# ard-nano-thermometer-4digit-display.net
KiCad netlist of a schematic drawn in EAGLE
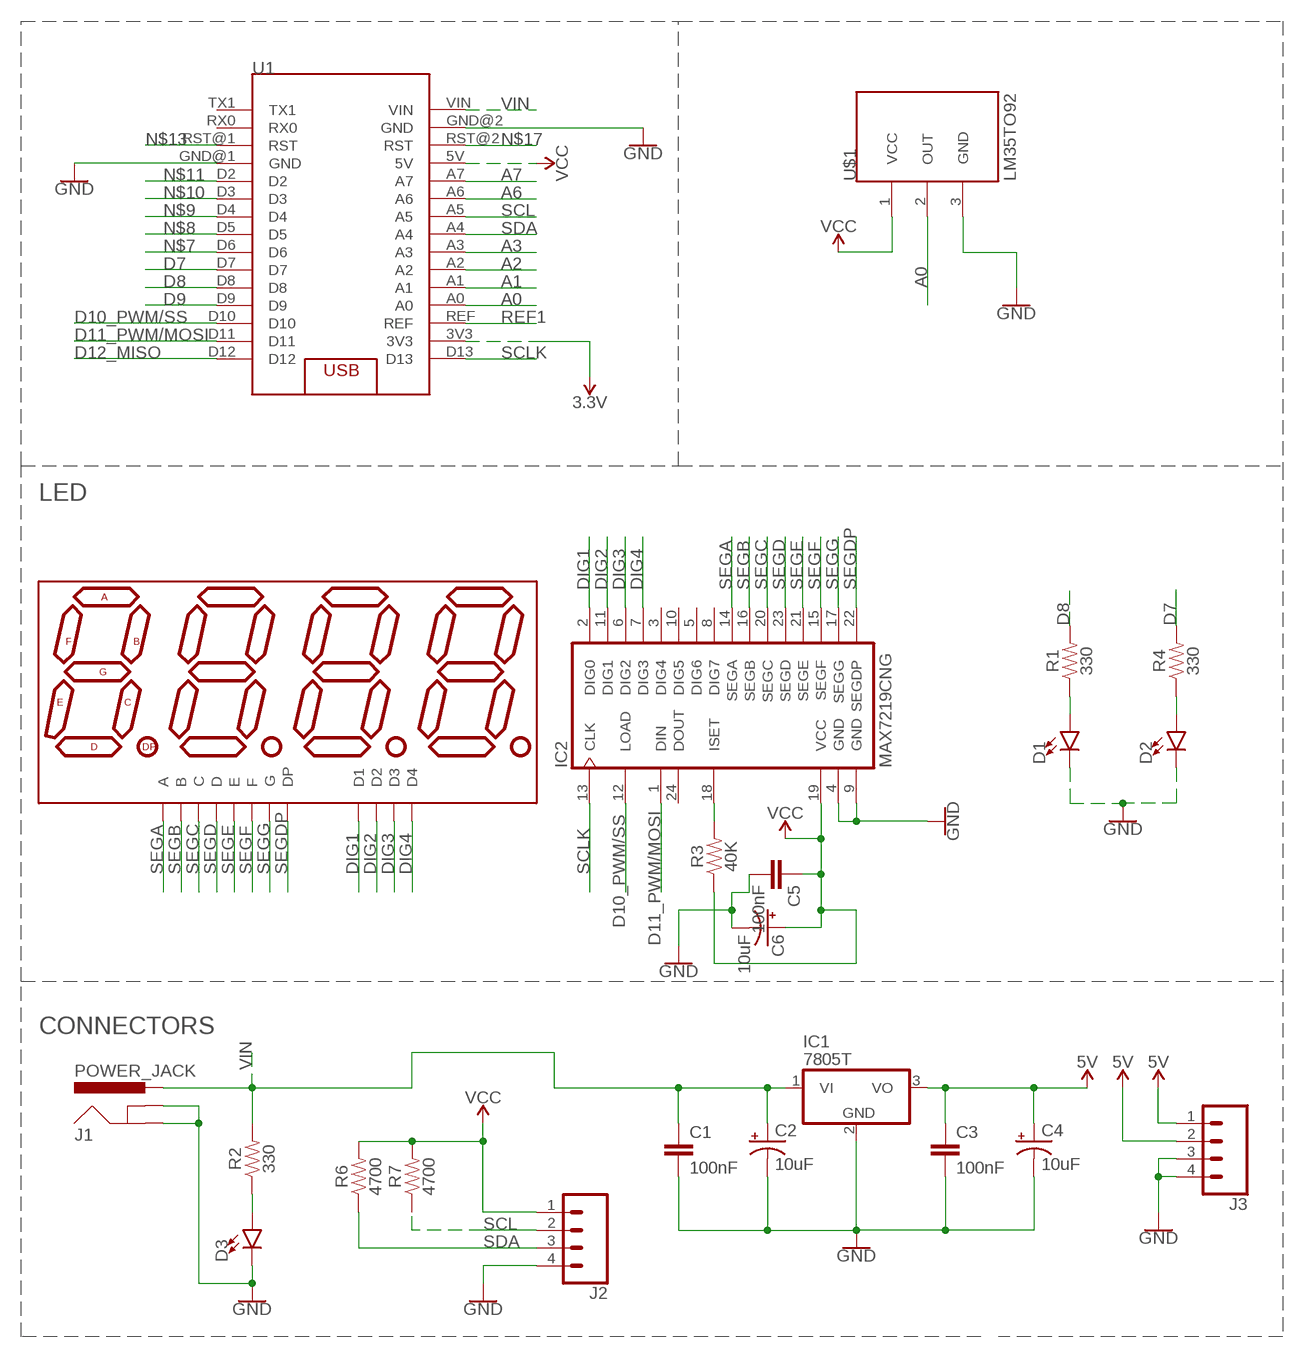
[diagram p0: schematic, sheet 1]

(export (version "E")
  (design (tool "Eeschema 10.0.6"))
  (components
    (comp (ref "C1")
      (value "100nF")
      (footprint "eagle-import:CAP-PTH-10MM")
      (libsource (lib "eagle-import") (part "10NF-PTH-10MM-10000V-1-%"))
    )
    (comp (ref "C2")
      (value "10uF")
      (footprint "eagle-import:CPOL-RADIAL-2.5MM-5MM")
      (libsource (lib "eagle-import") (part "10UF-POLAR-RADIAL-2.5MM-25V-20%"))
    )
    (comp (ref "C3")
      (value "100nF")
      (footprint "eagle-import:CAP-PTH-10MM")
      (libsource (lib "eagle-import") (part "10NF-PTH-10MM-10000V-1-%"))
    )
    (comp (ref "C4")
      (value "10uF")
      (footprint "eagle-import:CPOL-RADIAL-2.5MM-5MM")
      (libsource (lib "eagle-import") (part "10UF-POLAR-RADIAL-2.5MM-25V-20%"))
    )
    (comp (ref "C5")
      (value "100nF")
      (footprint "eagle-import:CAP-PTH-10MM")
      (libsource (lib "eagle-import") (part "10NF-PTH-10MM-10000V-1-%"))
    )
    (comp (ref "C6")
      (value "10uF")
      (footprint "eagle-import:CPOL-RADIAL-2.5MM-5MM")
      (libsource (lib "eagle-import") (part "10UF-POLAR-RADIAL-2.5MM-25V-20%"))
    )
    (comp (ref "D1")
      (value "LED3MM")
      (footprint "eagle-import:LED_3MM")
      (libsource (lib "eagle-import") (part "LED3MM"))
    )
    (comp (ref "D2")
      (value "LED3MM")
      (footprint "eagle-import:LED_3MM")
      (libsource (lib "eagle-import") (part "LED3MM"))
    )
    (comp (ref "D3")
      (value "LED3MM")
      (footprint "eagle-import:LED_3MM")
      (libsource (lib "eagle-import") (part "LED3MM"))
    )
    (comp (ref "DISP1")
      (value "ATA8041AB")
      (footprint "eagle-import:7-SEGMENT-4DIGIT-20MM")
      (libsource (lib "eagle-import") (part "7-SEGMENT-4DIGIT-20MM-BLUE"))
    )
    (comp (ref "IC1")
      (value "7805T")
      (footprint "eagle-import:TO220H")
      (libsource (lib "eagle-import") (part "78T05"))
    )
    (comp (ref "IC2")
      (value "MAX7219CNG")
      (footprint "eagle-import:DIL24-3")
      (fields (field (name "MF") "MAXIM"))
      (libsource (lib "eagle-import") (part "MAX7219CNG"))
    )
    (comp (ref "J1")
      (value "POWER_JACK")
      (footprint "eagle-import:POWER_JACK_PTH")
      (libsource (lib "eagle-import") (part "POWER_JACK"))
    )
    (comp (ref "J2")
      (value "CONN_04PTH")
      (footprint "eagle-import:1X04")
      (libsource (lib "eagle-import") (part "CONN_04PTH"))
    )
    (comp (ref "J3")
      (value "CONN_04PTH")
      (footprint "eagle-import:1X04")
      (libsource (lib "eagle-import") (part "CONN_04PTH"))
    )
    (comp (ref "R1")
      (value "330")
      (footprint "eagle-import:AXIAL-0.3")
      (libsource (lib "eagle-import") (part "1KOHM-HORIZ-1/4W-5%"))
    )
    (comp (ref "R2")
      (value "330")
      (footprint "eagle-import:AXIAL-0.3")
      (libsource (lib "eagle-import") (part "1KOHM-HORIZ-1/4W-5%"))
    )
    (comp (ref "R3")
      (value "40K")
      (footprint "eagle-import:AXIAL-0.3")
      (libsource (lib "eagle-import") (part "1KOHM-HORIZ-1/4W-1%"))
    )
    (comp (ref "R4")
      (value "330")
      (footprint "eagle-import:AXIAL-0.3")
      (libsource (lib "eagle-import") (part "1KOHM-HORIZ-1/4W-5%"))
    )
    (comp (ref "R6")
      (value "4700")
      (footprint "eagle-import:AXIAL-0.3")
      (libsource (lib "eagle-import") (part "1KOHM-HORIZ-1/4W-1%"))
    )
    (comp (ref "R7")
      (value "4700")
      (footprint "eagle-import:AXIAL-0.3")
      (libsource (lib "eagle-import") (part "1KOHM-HORIZ-1/4W-1%"))
    )
    (comp (ref "U$1")
      (value "LM35TO92")
      (footprint "eagle-import:LM35TO92")
      (libsource (lib "eagle-import") (part "LM35TO92"))
    )
    (comp (ref "U1")
      (value "ARDUINO_NANO")
      (footprint "eagle-import:ARDUINO_NANO")
      (libsource (lib "eagle-import") (part "ARDUINO_NANO"))
    )
  )
  (nets
    (net (code "1") (name "/A0") (class "Default")
      (node (ref "U$1") (pin "2") (pinfunction "OUT_2") (pintype "bidirectional"))
      (node (ref "U1") (pin "A0") (pinfunction "A0_A0") (pintype "bidirectional"))
    )
    (net (code "2") (name "/A1") (class "Default")
      (node (ref "U1") (pin "A1") (pinfunction "A1_A1") (pintype "bidirectional"))
    )
    (net (code "3") (name "/A2") (class "Default")
      (node (ref "U1") (pin "A2") (pinfunction "A2_A2") (pintype "bidirectional"))
    )
    (net (code "4") (name "/A3") (class "Default")
      (node (ref "U1") (pin "A3") (pinfunction "A3_A3") (pintype "bidirectional"))
    )
    (net (code "5") (name "/A6") (class "Default")
      (node (ref "U1") (pin "A6") (pinfunction "A6_A6") (pintype "bidirectional"))
    )
    (net (code "6") (name "/A7") (class "Default")
      (node (ref "U1") (pin "A7") (pinfunction "A7_A7") (pintype "bidirectional"))
    )
    (net (code "7") (name "/D7") (class "Default")
      (node (ref "R4") (pin "P$2") (pinfunction "2_P$2") (pintype "passive"))
      (node (ref "U1") (pin "D7") (pinfunction "D7_D7") (pintype "bidirectional"))
    )
    (net (code "8") (name "/D8") (class "Default")
      (node (ref "R1") (pin "P$2") (pinfunction "2_P$2") (pintype "passive"))
      (node (ref "U1") (pin "D8") (pinfunction "D8_D8") (pintype "bidirectional"))
    )
    (net (code "9") (name "/D9") (class "Default")
      (node (ref "U1") (pin "D9") (pinfunction "D9_D9") (pintype "bidirectional"))
    )
    (net (code "10") (name "/D10_PWM{slash}SS") (class "Default")
      (node (ref "IC2") (pin "12") (pinfunction "LOAD_12") (pintype "input"))
      (node (ref "U1") (pin "D10") (pinfunction "D10_D10") (pintype "bidirectional"))
    )
    (net (code "11") (name "/D11_PWM{slash}MOSI") (class "Default")
      (node (ref "IC2") (pin "1") (pinfunction "DIN_1") (pintype "input"))
      (node (ref "U1") (pin "D11") (pinfunction "D11_D11") (pintype "bidirectional"))
    )
    (net (code "12") (name "/D12_MISO") (class "Default")
      (node (ref "U1") (pin "D12") (pinfunction "D12_D12") (pintype "bidirectional"))
    )
    (net (code "13") (name "/DIG1") (class "Default")
      (node (ref "DISP1") (pin "12") (pinfunction "D1_12") (pintype "bidirectional"))
      (node (ref "IC2") (pin "2") (pinfunction "DIG0_2") (pintype "output"))
    )
    (net (code "14") (name "/DIG2") (class "Default")
      (node (ref "DISP1") (pin "9") (pinfunction "D2_9") (pintype "bidirectional"))
      (node (ref "IC2") (pin "11") (pinfunction "DIG1_11") (pintype "output"))
    )
    (net (code "15") (name "/DIG3") (class "Default")
      (node (ref "DISP1") (pin "8") (pinfunction "D3_8") (pintype "bidirectional"))
      (node (ref "IC2") (pin "6") (pinfunction "DIG2_6") (pintype "output"))
    )
    (net (code "16") (name "/DIG4") (class "Default")
      (node (ref "DISP1") (pin "6") (pinfunction "D4_6") (pintype "bidirectional"))
      (node (ref "IC2") (pin "7") (pinfunction "DIG3_7") (pintype "output"))
    )
    (net (code "17") (name "/N$7") (class "Default")
      (node (ref "U1") (pin "D6") (pinfunction "D6_D6") (pintype "bidirectional"))
    )
    (net (code "18") (name "/N$8") (class "Default")
      (node (ref "U1") (pin "D5") (pinfunction "D5_D5") (pintype "bidirectional"))
    )
    (net (code "19") (name "/N$9") (class "Default")
      (node (ref "U1") (pin "D4") (pinfunction "D4_D4") (pintype "bidirectional"))
    )
    (net (code "20") (name "/N$10") (class "Default")
      (node (ref "U1") (pin "D3") (pinfunction "D3_D3") (pintype "bidirectional"))
    )
    (net (code "21") (name "/N$11") (class "Default")
      (node (ref "U1") (pin "D2") (pinfunction "D2_D2") (pintype "bidirectional"))
    )
    (net (code "22") (name "/N$13") (class "Default")
      (node (ref "U1") (pin "RST@1") (pinfunction "RST_RST@1") (pintype "bidirectional"))
    )
    (net (code "23") (name "/N$17") (class "Default")
      (node (ref "U1") (pin "RST@2") (pinfunction "RST_RST@2") (pintype "bidirectional"))
    )
    (net (code "24") (name "/REF1") (class "Default")
      (node (ref "U1") (pin "REF") (pinfunction "REF_REF") (pintype "bidirectional"))
    )
    (net (code "25") (name "/SCL") (class "Default")
      (node (ref "J2") (pin "2") (pinfunction "2_2") (pintype "passive"))
      (node (ref "R7") (pin "P$1") (pinfunction "1_P$1") (pintype "passive"))
      (node (ref "U1") (pin "A5") (pinfunction "A5_A5") (pintype "bidirectional"))
    )
    (net (code "26") (name "/SCLK") (class "Default")
      (node (ref "IC2") (pin "13") (pinfunction "CLK_13") (pintype "input"))
      (node (ref "U1") (pin "D13") (pinfunction "D13_D13") (pintype "bidirectional"))
    )
    (net (code "27") (name "/SDA") (class "Default")
      (node (ref "J2") (pin "3") (pinfunction "3_3") (pintype "passive"))
      (node (ref "R6") (pin "P$1") (pinfunction "1_P$1") (pintype "passive"))
      (node (ref "U1") (pin "A4") (pinfunction "A4_A4") (pintype "bidirectional"))
    )
    (net (code "28") (name "/SEGA") (class "Default")
      (node (ref "DISP1") (pin "11") (pinfunction "A_11") (pintype "bidirectional"))
      (node (ref "IC2") (pin "14") (pinfunction "SEGA_14") (pintype "output"))
    )
    (net (code "29") (name "/SEGB") (class "Default")
      (node (ref "DISP1") (pin "7") (pinfunction "B_7") (pintype "bidirectional"))
      (node (ref "IC2") (pin "16") (pinfunction "SEGB_16") (pintype "output"))
    )
    (net (code "30") (name "/SEGC") (class "Default")
      (node (ref "DISP1") (pin "4") (pinfunction "C_4") (pintype "bidirectional"))
      (node (ref "IC2") (pin "20") (pinfunction "SEGC_20") (pintype "output"))
    )
    (net (code "31") (name "/SEGD") (class "Default")
      (node (ref "DISP1") (pin "2") (pinfunction "D_2") (pintype "bidirectional"))
      (node (ref "IC2") (pin "23") (pinfunction "SEGD_23") (pintype "output"))
    )
    (net (code "32") (name "/SEGDP") (class "Default")
      (node (ref "DISP1") (pin "3") (pinfunction "DP_3") (pintype "bidirectional"))
      (node (ref "IC2") (pin "22") (pinfunction "SEGDP_22") (pintype "output"))
    )
    (net (code "33") (name "/SEGE") (class "Default")
      (node (ref "DISP1") (pin "1") (pinfunction "E_1") (pintype "bidirectional"))
      (node (ref "IC2") (pin "21") (pinfunction "SEGE_21") (pintype "output"))
    )
    (net (code "34") (name "/SEGF") (class "Default")
      (node (ref "DISP1") (pin "10") (pinfunction "F_10") (pintype "bidirectional"))
      (node (ref "IC2") (pin "15") (pinfunction "SEGF_15") (pintype "output"))
    )
    (net (code "35") (name "/SEGG") (class "Default")
      (node (ref "DISP1") (pin "5") (pinfunction "G_5") (pintype "bidirectional"))
      (node (ref "IC2") (pin "17") (pinfunction "SEGG_17") (pintype "output"))
    )
    (net (code "36") (name "/VIN") (class "Default")
      (node (ref "C1") (pin "1") (pinfunction "1_1") (pintype "passive"))
      (node (ref "C2") (pin "1") (pinfunction "+_1") (pintype "passive"))
      (node (ref "IC1") (pin "1") (pinfunction "VI_1") (pintype "input"))
      (node (ref "J1") (pin "PWR") (pinfunction "PWR_PWR") (pintype "bidirectional"))
      (node (ref "R2") (pin "P$2") (pinfunction "2_P$2") (pintype "passive"))
      (node (ref "U1") (pin "VIN") (pinfunction "VIN_VIN") (pintype "bidirectional"))
    )
    (net (code "37") (name "3.3V") (class "Default")
      (node (ref "U1") (pin "3V3") (pinfunction "3V3_3V3") (pintype "bidirectional"))
    )
    (net (code "38") (name "5V") (class "Default")
      (node (ref "C3") (pin "1") (pinfunction "1_1") (pintype "passive"))
      (node (ref "C4") (pin "1") (pinfunction "+_1") (pintype "passive"))
      (node (ref "IC1") (pin "3") (pinfunction "VO_3") (pintype "passive"))
      (node (ref "J3") (pin "1") (pinfunction "1_1") (pintype "passive"))
      (node (ref "J3") (pin "2") (pinfunction "2_2") (pintype "passive"))
    )
    (net (code "39") (name "GND") (class "Default")
      (node (ref "C1") (pin "2") (pinfunction "2_2") (pintype "passive"))
      (node (ref "C2") (pin "2") (pinfunction "-_2") (pintype "passive"))
      (node (ref "C3") (pin "2") (pinfunction "2_2") (pintype "passive"))
      (node (ref "C4") (pin "2") (pinfunction "-_2") (pintype "passive"))
      (node (ref "C5") (pin "2") (pinfunction "2_2") (pintype "passive"))
      (node (ref "C6") (pin "2") (pinfunction "-_2") (pintype "passive"))
      (node (ref "D1") (pin "K") (pinfunction "C_K") (pintype "passive"))
      (node (ref "D2") (pin "K") (pinfunction "C_K") (pintype "passive"))
      (node (ref "D3") (pin "K") (pinfunction "C_K") (pintype "passive"))
      (node (ref "IC1") (pin "2") (pinfunction "GND_2") (pintype "passive"))
      (node (ref "IC2") (pin "4") (pinfunction "GND_4") (pintype "power_in"))
      (node (ref "IC2") (pin "9") (pinfunction "GND_9") (pintype "power_in"))
      (node (ref "J1") (pin "GND") (pinfunction "GND_GND") (pintype "bidirectional"))
      (node (ref "J1") (pin "GNDBREAK") (pinfunction "GNDBREAK_GNDBREAK") (pintype "bidirectional"))
      (node (ref "J2") (pin "4") (pinfunction "4_4") (pintype "passive"))
      (node (ref "J3") (pin "3") (pinfunction "3_3") (pintype "passive"))
      (node (ref "J3") (pin "4") (pinfunction "4_4") (pintype "passive"))
      (node (ref "U$1") (pin "3") (pinfunction "GND_3") (pintype "bidirectional"))
      (node (ref "U1") (pin "GND@1") (pinfunction "GND_GND@1") (pintype "bidirectional"))
      (node (ref "U1") (pin "GND@2") (pinfunction "GND_GND@2") (pintype "bidirectional"))
    )
    (net (code "40") (name "Net-(IC2-ISET)") (class "Default")
      (node (ref "IC2") (pin "18") (pinfunction "ISET_18") (pintype "input"))
      (node (ref "R3") (pin "P$2") (pinfunction "2_P$2") (pintype "passive"))
    )
    (net (code "41") (name "Net-(R1-1)") (class "Default")
      (node (ref "D1") (pin "A") (pinfunction "A_A") (pintype "passive"))
      (node (ref "R1") (pin "P$1") (pinfunction "1_P$1") (pintype "passive"))
    )
    (net (code "42") (name "Net-(R2-1)") (class "Default")
      (node (ref "D3") (pin "A") (pinfunction "A_A") (pintype "passive"))
      (node (ref "R2") (pin "P$1") (pinfunction "1_P$1") (pintype "passive"))
    )
    (net (code "43") (name "Net-(R4-1)") (class "Default")
      (node (ref "D2") (pin "A") (pinfunction "A_A") (pintype "passive"))
      (node (ref "R4") (pin "P$1") (pinfunction "1_P$1") (pintype "passive"))
    )
    (net (code "44") (name "VCC") (class "Default")
      (node (ref "C5") (pin "1") (pinfunction "1_1") (pintype "passive"))
      (node (ref "C6") (pin "1") (pinfunction "+_1") (pintype "passive"))
      (node (ref "IC2") (pin "19") (pinfunction "VCC_19") (pintype "power_in"))
      (node (ref "J2") (pin "1") (pinfunction "1_1") (pintype "passive"))
      (node (ref "R3") (pin "P$1") (pinfunction "1_P$1") (pintype "passive"))
      (node (ref "R6") (pin "P$2") (pinfunction "2_P$2") (pintype "passive"))
      (node (ref "R7") (pin "P$2") (pinfunction "2_P$2") (pintype "passive"))
      (node (ref "U$1") (pin "1") (pinfunction "VCC_1") (pintype "bidirectional"))
      (node (ref "U1") (pin "5V") (pinfunction "5V_5V") (pintype "bidirectional"))
    )
    (net (code "45") (name "unconnected-(IC2-DIG4-Pad3)") (class "Default")
      (node (ref "IC2") (pin "3") (pinfunction "DIG4_3") (pintype "output"))
    )
    (net (code "46") (name "unconnected-(IC2-DIG5-Pad10)") (class "Default")
      (node (ref "IC2") (pin "10") (pinfunction "DIG5_10") (pintype "output"))
    )
    (net (code "47") (name "unconnected-(IC2-DIG6-Pad5)") (class "Default")
      (node (ref "IC2") (pin "5") (pinfunction "DIG6_5") (pintype "output"))
    )
    (net (code "48") (name "unconnected-(IC2-DIG7-Pad8)") (class "Default")
      (node (ref "IC2") (pin "8") (pinfunction "DIG7_8") (pintype "output"))
    )
    (net (code "49") (name "unconnected-(IC2-DOUT-Pad24)") (class "Default")
      (node (ref "IC2") (pin "24") (pinfunction "DOUT_24") (pintype "output"))
    )
    (net (code "50") (name "unconnected-(U1-PadRX0)") (class "Default")
      (node (ref "U1") (pin "RX0") (pinfunction "RX0_RX0") (pintype "bidirectional"))
    )
    (net (code "51") (name "unconnected-(U1-PadTX1)") (class "Default")
      (node (ref "U1") (pin "TX1") (pinfunction "TX1_TX1") (pintype "bidirectional"))
    )
  )
)
